# CAN.net
KiCad netlist of a schematic drawn in Altium Designer
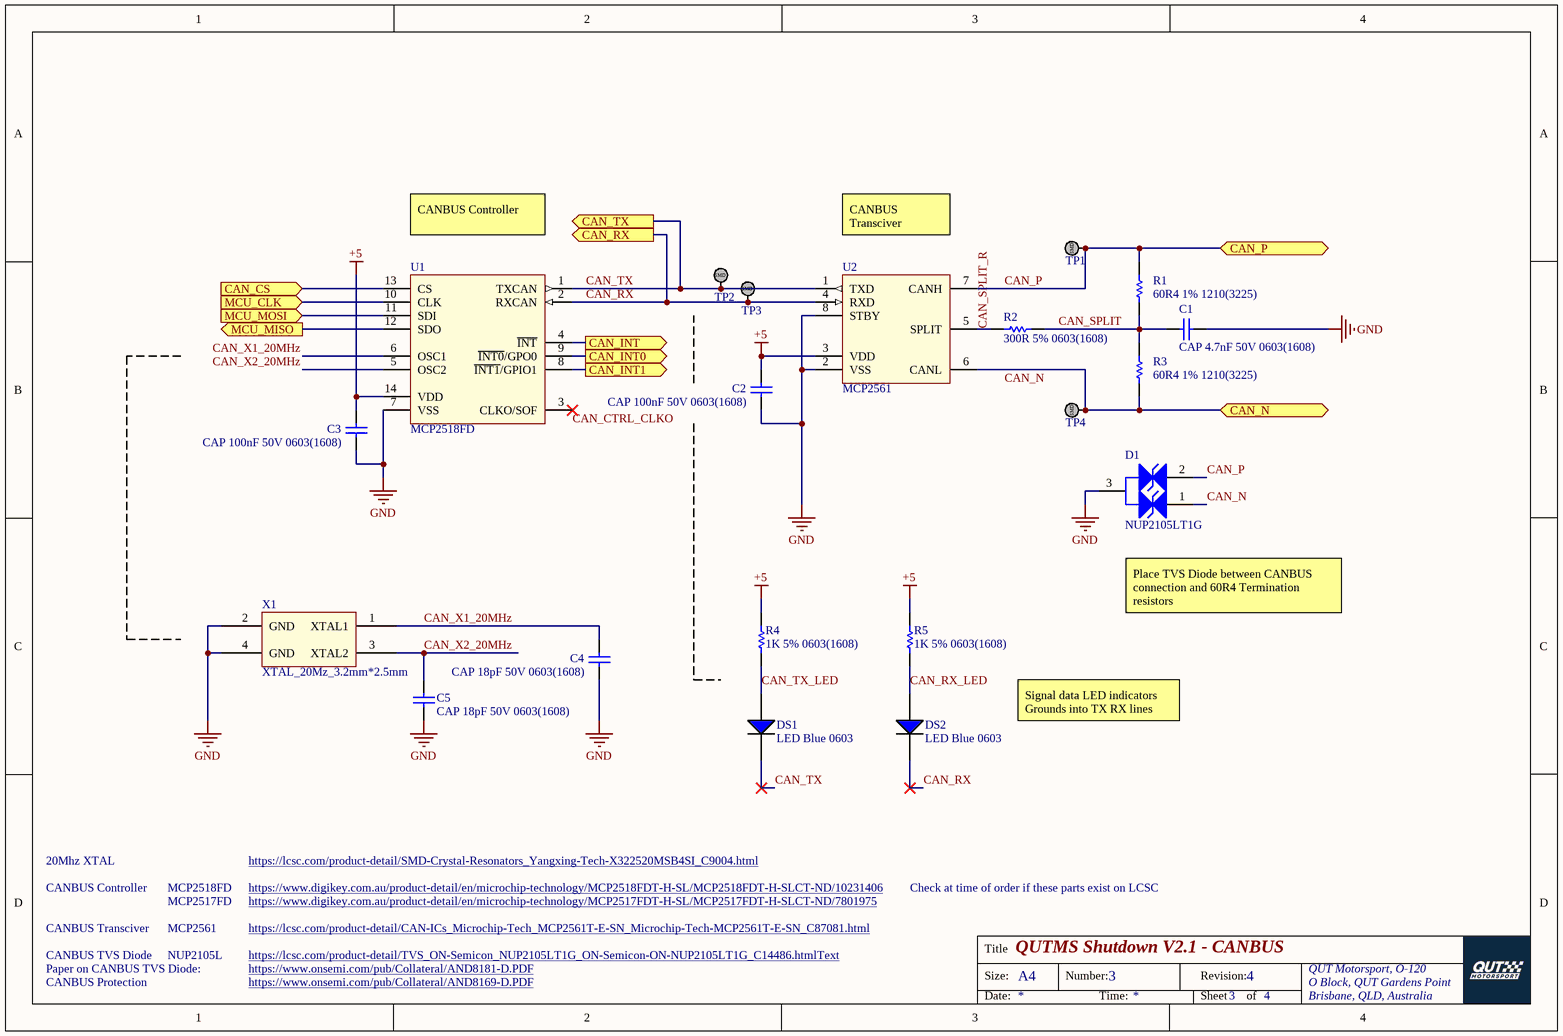
[diagram p0: CAN.SchDoc]

(export (version "E")
  (design (tool "Eeschema 10.0.6"))
  (components
    (comp (ref "C1")
      (value "CAP 4.7nF 50V 0603(1608)")
      (footprint "CAPC0603(1608)100_M")
      (description "CAP 4.7nF 50V ±5% 0603 (1608 Metric) Thickness 1mm SMD")
      (fields (field (name "TOLERANCE") "Â±5%"))
      (libsource (lib "Altium Content Vault") (part "CAP"))
    )
    (comp (ref "C2")
      (value "CAP 100nF 50V 0603(1608)")
      (footprint "CAPC0603(1608)100_L")
      (description "CAP 100nF 50V ±5% 0603 (1608 Metric) Thickness 1mm SMD")
      (fields (field (name "TOLERANCE") "Â±5%"))
      (libsource (lib "Altium Content Vault") (part "CAP"))
    )
    (comp (ref "C3")
      (value "CAP 100nF 50V 0603(1608)")
      (footprint "CAPC0603(1608)100_L")
      (description "CAP 100nF 50V ±5% 0603 (1608 Metric) Thickness 1mm SMD")
      (fields (field (name "TOLERANCE") "Â±5%"))
      (libsource (lib "Altium Content Vault") (part "CAP"))
    )
    (comp (ref "C4")
      (value "CAP 18pF 50V 0603(1608)")
      (footprint "CAPC0603(1608)100_L")
      (description "CAP 18pF 50V ±1% 0603 (1608 Metric) Thickness 1mm SMD")
      (fields (field (name "TOLERANCE") "Â±1%"))
      (libsource (lib "Altium Content Vault") (part "CAP"))
    )
    (comp (ref "C5")
      (value "CAP 18pF 50V 0603(1608)")
      (footprint "CAPC0603(1608)100_L")
      (description "CAP 18pF 50V ±1% 0603 (1608 Metric) Thickness 1mm SMD")
      (fields (field (name "TOLERANCE") "Â±1%"))
      (libsource (lib "Altium Content Vault") (part "CAP"))
    )
    (comp (ref "D1")
      (value "NUP2105LT1G")
      (footprint "ONSC-SOT-23-3-318-08_V")
      (description "Dual Line CAN Bus Protector, 3-Pin SOT-23, Pb-Free, Tape and Reel")
      (fields (field (name "MANUFACTURER") "On Semiconductor"))
      (libsource (lib "Altium Content Vault") (part "ONSC-NUP21X5X-SOT-23-3-318-08"))
    )
    (comp (ref "DS1")
      (value "LED Blue 0603")
      (footprint "LED BLUE 0603")
      (libsource (lib "QUTMS_LEDLibrary") (part "LED BLUE 0603"))
    )
    (comp (ref "DS2")
      (value "LED Blue 0603")
      (footprint "LED BLUE 0603")
      (libsource (lib "QUTMS_LEDLibrary") (part "LED BLUE 0603"))
    )
    (comp (ref "R1")
      (value "60R4 1% 1210(3225)")
      (footprint "RESC1210(3225)_L")
      (description "60R4 0.5W 1% 1210 (3225 Metric)  SMD")
      (fields (field (name "TOLERANCE") "1 %") (field (name "POWER") "0.5 W"))
      (libsource (lib "Altium Content Vault") (part "RES"))
    )
    (comp (ref "R2")
      (value "300R 5% 0603(1608)")
      (footprint "RESC0603(1608)_N")
      (description "300R 0.1W 5% 0603 (1608 Metric)  SMD")
      (fields (field (name "TOLERANCE") "5 %") (field (name "POWER") "0.1 W"))
      (libsource (lib "Altium Content Vault") (part "RES"))
    )
    (comp (ref "R3")
      (value "60R4 1% 1210(3225)")
      (footprint "RESC1210(3225)_L")
      (description "60R4 0.5W 1% 1210 (3225 Metric)  SMD")
      (fields (field (name "TOLERANCE") "1 %") (field (name "POWER") "0.5 W"))
      (libsource (lib "Altium Content Vault") (part "RES"))
    )
    (comp (ref "R4")
      (value "1K 5% 0603(1608)")
      (footprint "RESC0603(1608)_L")
      (description "1K 0.1W 5% 0603 (1608 Metric)  SMD")
      (fields (field (name "TOLERANCE") "5 %") (field (name "POWER") "0.1 W"))
      (libsource (lib "Altium Content Vault") (part "RES"))
    )
    (comp (ref "R5")
      (value "1K 5% 0603(1608)")
      (footprint "RESC0603(1608)_L")
      (description "1K 0.1W 5% 0603 (1608 Metric)  SMD")
      (fields (field (name "TOLERANCE") "5 %") (field (name "POWER") "0.1 W"))
      (libsource (lib "Altium Content Vault") (part "RES"))
    )
    (comp (ref "TP1")
      (value "TestPoint_SMD")
      (footprint "TestPointSMD")
      (libsource (lib "StandardTest") (part "TestPoint_SMD"))
    )
    (comp (ref "TP2")
      (value "TestPoint_SMD")
      (footprint "TestPointSMD")
      (libsource (lib "StandardTest") (part "TestPoint_SMD"))
    )
    (comp (ref "TP3")
      (value "TestPoint_SMD")
      (footprint "TestPointSMD")
      (libsource (lib "StandardTest") (part "TestPoint_SMD"))
    )
    (comp (ref "TP4")
      (value "TestPoint_SMD")
      (footprint "TestPointSMD")
      (libsource (lib "StandardTest") (part "TestPoint_SMD"))
    )
    (comp (ref "U1")
      (value "MCP2518FD")
      (footprint "MCP2517FD SOIC")
      (libsource (lib "QUTMS_CANLibrary") (part "MCP2518FD"))
    )
    (comp (ref "U2")
      (value "MCP2561")
      (footprint "MCP2561 SOIC")
      (libsource (lib "QUTMS_CANLibrary") (part "MCP2561"))
    )
    (comp (ref "X1")
      (value "XTAL_20Mz_3.2mm*2.5mm")
      (footprint "3.2mm*2.5mm")
      (libsource (lib "QUTMS_CrystalLibrary") (part "XTAL_20Mz_3.2mm*2.5mm"))
    )
  )
  (nets
    (net (code "1") (name "+5") (class "Default")
      (node (ref "C2") (pin "2") (pinfunction "2_2") (pintype "passive"))
      (node (ref "C3") (pin "2") (pinfunction "2_2") (pintype "passive"))
      (node (ref "R4") (pin "2") (pinfunction "2_2") (pintype "passive"))
      (node (ref "R5") (pin "2") (pinfunction "2_2") (pintype "passive"))
      (node (ref "U1") (pin "14") (pinfunction "VDD_14") (pintype "passive"))
      (node (ref "U2") (pin "3") (pinfunction "VDD_3") (pintype "passive"))
    )
    (net (code "2") (name "/CAN_CS") (class "Default")
      (node (ref "U1") (pin "13") (pinfunction "CS_13") (pintype "passive"))
    )
    (net (code "3") (name "/CAN_CTRL_CLKO") (class "Default")
      (node (ref "U1") (pin "3") (pinfunction "CLKO/SOF_3") (pintype "passive+no_connect"))
    )
    (net (code "4") (name "/CAN_INT") (class "Default")
      (node (ref "U1") (pin "4") (pinfunction "~{INT}_4") (pintype "passive"))
    )
    (net (code "5") (name "/CAN_INT0") (class "Default")
      (node (ref "U1") (pin "9") (pinfunction "~{INT0}/GPO0_9") (pintype "passive"))
    )
    (net (code "6") (name "/CAN_INT1") (class "Default")
      (node (ref "U1") (pin "8") (pinfunction "~{INT1}/GPIO1_8") (pintype "passive"))
    )
    (net (code "7") (name "/CAN_N") (class "Default")
      (node (ref "D1") (pin "1") (pinfunction "K_1") (pintype "passive"))
      (node (ref "R3") (pin "1") (pinfunction "1_1") (pintype "passive"))
      (node (ref "TP4") (pin "1") (pinfunction "1_1") (pintype "passive"))
      (node (ref "U2") (pin "6") (pinfunction "CANL_6") (pintype "passive"))
    )
    (net (code "8") (name "/CAN_P") (class "Default")
      (node (ref "D1") (pin "2") (pinfunction "K_2") (pintype "passive"))
      (node (ref "R1") (pin "2") (pinfunction "2_2") (pintype "passive"))
      (node (ref "TP1") (pin "1") (pinfunction "1_1") (pintype "passive"))
      (node (ref "U2") (pin "7") (pinfunction "CANH_7") (pintype "passive"))
    )
    (net (code "9") (name "/CAN_RX") (class "Default")
      (node (ref "DS2") (pin "2") (pinfunction "C_2") (pintype "passive"))
      (node (ref "TP3") (pin "1") (pinfunction "1_1") (pintype "passive"))
      (node (ref "U1") (pin "2") (pinfunction "RXCAN_2") (pintype "input"))
      (node (ref "U2") (pin "4") (pinfunction "RXD_4") (pintype "input"))
    )
    (net (code "10") (name "/CAN_RX_LED") (class "Default")
      (node (ref "DS2") (pin "1") (pinfunction "A_1") (pintype "passive"))
      (node (ref "R5") (pin "1") (pinfunction "1_1") (pintype "passive"))
    )
    (net (code "11") (name "/CAN_SPLIT") (class "Default")
      (node (ref "C1") (pin "2") (pinfunction "2_2") (pintype "passive"))
      (node (ref "R1") (pin "1") (pinfunction "1_1") (pintype "passive"))
      (node (ref "R2") (pin "2") (pinfunction "2_2") (pintype "passive"))
      (node (ref "R3") (pin "2") (pinfunction "2_2") (pintype "passive"))
    )
    (net (code "12") (name "/CAN_SPLIT_R") (class "Default")
      (node (ref "R2") (pin "1") (pinfunction "1_1") (pintype "passive"))
      (node (ref "U2") (pin "5") (pinfunction "SPLIT_5") (pintype "passive"))
    )
    (net (code "13") (name "/CAN_TX") (class "Default")
      (node (ref "DS1") (pin "2") (pinfunction "C_2") (pintype "passive"))
      (node (ref "TP2") (pin "1") (pinfunction "1_1") (pintype "passive"))
      (node (ref "U1") (pin "1") (pinfunction "TXCAN_1") (pintype "output"))
      (node (ref "U2") (pin "1") (pinfunction "TXD_1") (pintype "output"))
    )
    (net (code "14") (name "/CAN_TX_LED") (class "Default")
      (node (ref "DS1") (pin "1") (pinfunction "A_1") (pintype "passive"))
      (node (ref "R4") (pin "1") (pinfunction "1_1") (pintype "passive"))
    )
    (net (code "15") (name "/CAN_X1_20MHz") (class "Default")
      (node (ref "C4") (pin "2") (pinfunction "2_2") (pintype "passive"))
      (node (ref "U1") (pin "6") (pinfunction "OSC1_6") (pintype "passive"))
      (node (ref "X1") (pin "1") (pinfunction "XTAL1_1") (pintype "passive"))
    )
    (net (code "16") (name "/CAN_X2_20MHz") (class "Default")
      (node (ref "C5") (pin "2") (pinfunction "2_2") (pintype "passive"))
      (node (ref "U1") (pin "5") (pinfunction "OSC2_5") (pintype "passive"))
      (node (ref "X1") (pin "3") (pinfunction "XTAL2_3") (pintype "passive"))
    )
    (net (code "17") (name "/MCU_CLK") (class "Default")
      (node (ref "U1") (pin "10") (pinfunction "CLK_10") (pintype "passive"))
    )
    (net (code "18") (name "/MCU_MISO") (class "Default")
      (node (ref "U1") (pin "12") (pinfunction "SDO_12") (pintype "passive"))
    )
    (net (code "19") (name "/MCU_MOSI") (class "Default")
      (node (ref "U1") (pin "11") (pinfunction "SDI_11") (pintype "passive"))
    )
    (net (code "20") (name "GND") (class "Default")
      (node (ref "C1") (pin "1") (pinfunction "1_1") (pintype "passive"))
      (node (ref "C2") (pin "1") (pinfunction "1_1") (pintype "passive"))
      (node (ref "C3") (pin "1") (pinfunction "1_1") (pintype "passive"))
      (node (ref "C4") (pin "1") (pinfunction "1_1") (pintype "passive"))
      (node (ref "C5") (pin "1") (pinfunction "1_1") (pintype "passive"))
      (node (ref "D1") (pin "3") (pinfunction "K_3") (pintype "passive"))
      (node (ref "U1") (pin "7") (pinfunction "VSS_7") (pintype "passive"))
      (node (ref "U2") (pin "2") (pinfunction "VSS_2") (pintype "passive"))
      (node (ref "U2") (pin "8") (pinfunction "STBY_8") (pintype "passive"))
      (node (ref "X1") (pin "2") (pinfunction "GND_2") (pintype "passive"))
      (node (ref "X1") (pin "4") (pinfunction "GND_4") (pintype "passive"))
    )
  )
)
